# usb-led.net
KiCad netlist of a schematic drawn in EAGLE
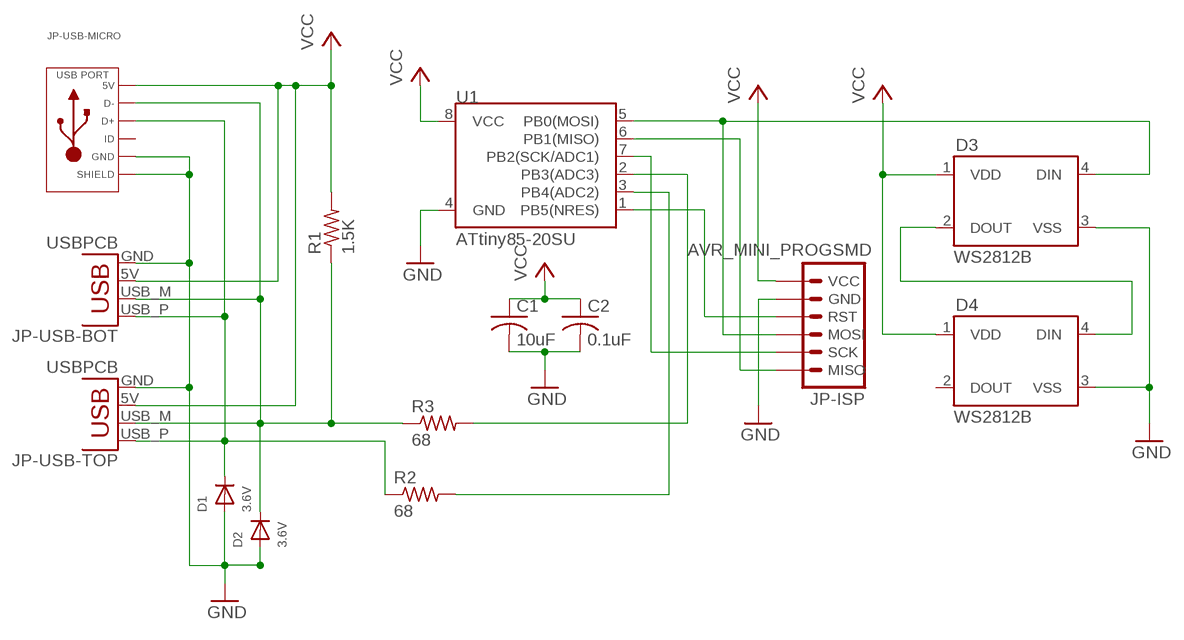
[diagram p0: schematic, sheet 1]

(export (version "E")
  (design (tool "Eeschema 10.0.6"))
  (components
    (comp (ref "C1")
      (value "10uF")
      (footprint "eagle-import:C0402")
      (libsource (lib "eagle-import") (part "C-USC0402"))
    )
    (comp (ref "C2")
      (value "0.1uF")
      (footprint "eagle-import:C0402")
      (libsource (lib "eagle-import") (part "C-USC0402"))
    )
    (comp (ref "D1")
      (value "3.6V")
      (footprint "eagle-import:SOD-523")
      (libsource (lib "eagle-import") (part "DIODESOD-523"))
    )
    (comp (ref "D2")
      (value "3.6V")
      (footprint "eagle-import:SOD-523")
      (libsource (lib "eagle-import") (part "DIODESOD-523"))
    )
    (comp (ref "D3")
      (value "WS2812B")
      (footprint "eagle-import:WS2812B")
      (libsource (lib "eagle-import") (part "WS2812B"))
    )
    (comp (ref "D4")
      (value "WS2812B")
      (footprint "eagle-import:WS2812B")
      (libsource (lib "eagle-import") (part "WS2812B"))
    )
    (comp (ref "JP-ISP")
      (value "AVR_MINI_PROGSMD")
      (footprint "eagle-import:AVR_MINI_PROG")
      (libsource (lib "eagle-import") (part "AVR_MINI_PROGSMD"))
    )
    (comp (ref "JP-USB-BOT")
      (value "USBPCB")
      (footprint "eagle-import:USB-A-PCB")
      (libsource (lib "eagle-import") (part "USBPCB"))
    )
    (comp (ref "JP-USB-MICRO")
      (value "USB_MICRO_RIGHT")
      (footprint "eagle-import:MICROUSB-RIGHT")
      (libsource (lib "eagle-import") (part "USB_MICRO_RIGHT"))
    )
    (comp (ref "JP-USB-TOP")
      (value "USBPCB")
      (footprint "eagle-import:USB-A-PCB")
      (libsource (lib "eagle-import") (part "USBPCB"))
    )
    (comp (ref "R1")
      (value "1.5K")
      (footprint "eagle-import:R0402")
      (libsource (lib "eagle-import") (part "R-US_R0402"))
    )
    (comp (ref "R2")
      (value "68")
      (footprint "eagle-import:R0402")
      (libsource (lib "eagle-import") (part "R-US_R0402"))
    )
    (comp (ref "R3")
      (value "68")
      (footprint "eagle-import:R0402")
      (libsource (lib "eagle-import") (part "R-US_R0402"))
    )
    (comp (ref "U1")
      (value "ATtiny85-20SU")
      (footprint "eagle-import:SO08-EIAJ")
      (libsource (lib "eagle-import") (part "ATTINY45TINY85-20-SMT"))
    )
  )
  (nets
    (net (code "1") (name "GND") (class "Default")
      (node (ref "C1") (pin "2") (pinfunction "2_2") (pintype "passive"))
      (node (ref "C2") (pin "2") (pinfunction "2_2") (pintype "passive"))
      (node (ref "D1") (pin "A") (pinfunction "A_A") (pintype "passive"))
      (node (ref "D2") (pin "A") (pinfunction "A_A") (pintype "passive"))
      (node (ref "D3") (pin "3") (pinfunction "VSS_3") (pintype "power_in"))
      (node (ref "D4") (pin "3") (pinfunction "VSS_3") (pintype "power_in"))
      (node (ref "JP-ISP") (pin "2") (pinfunction "GND_2") (pintype "passive"))
      (node (ref "JP-USB-BOT") (pin "GND") (pinfunction "GND_GND") (pintype "bidirectional"))
      (node (ref "JP-USB-MICRO") (pin "5") (pinfunction "GND_5") (pintype "power_in"))
      (node (ref "JP-USB-MICRO") (pin "S1") (pinfunction "SLD_S1") (pintype "power_in"))
      (node (ref "JP-USB-MICRO") (pin "S2") (pinfunction "SLD_S2") (pintype "power_in"))
      (node (ref "JP-USB-MICRO") (pin "S3") (pinfunction "SLD_S3") (pintype "power_in"))
      (node (ref "JP-USB-MICRO") (pin "S4") (pinfunction "SLD_S4") (pintype "power_in"))
      (node (ref "JP-USB-MICRO") (pin "S5") (pinfunction "SLD_S5") (pintype "power_in"))
      (node (ref "JP-USB-MICRO") (pin "S6") (pinfunction "SLD_S6") (pintype "power_in"))
      (node (ref "JP-USB-TOP") (pin "GND") (pinfunction "GND_GND") (pintype "bidirectional"))
      (node (ref "U1") (pin "4") (pinfunction "GND_4") (pintype "bidirectional"))
    )
    (net (code "2") (name "Net-(D1-C)") (class "Default")
      (node (ref "D1") (pin "K") (pinfunction "C_K") (pintype "passive"))
      (node (ref "JP-USB-BOT") (pin "USB_P") (pinfunction "D+_USB_P") (pintype "bidirectional"))
      (node (ref "JP-USB-MICRO") (pin "3") (pinfunction "D+_3") (pintype "bidirectional"))
      (node (ref "JP-USB-TOP") (pin "USB_P") (pinfunction "D+_USB_P") (pintype "bidirectional"))
      (node (ref "R2") (pin "1") (pinfunction "1_1") (pintype "passive"))
    )
    (net (code "3") (name "Net-(D2-C)") (class "Default")
      (node (ref "D2") (pin "K") (pinfunction "C_K") (pintype "passive"))
      (node (ref "JP-USB-BOT") (pin "USB_M") (pinfunction "D-_USB_M") (pintype "bidirectional"))
      (node (ref "JP-USB-MICRO") (pin "2") (pinfunction "D-_2") (pintype "bidirectional"))
      (node (ref "JP-USB-TOP") (pin "USB_M") (pinfunction "D-_USB_M") (pintype "bidirectional"))
      (node (ref "R1") (pin "1") (pinfunction "1_1") (pintype "passive"))
      (node (ref "R3") (pin "1") (pinfunction "1_1") (pintype "passive"))
    )
    (net (code "4") (name "Net-(D3-DIN)") (class "Default")
      (node (ref "D3") (pin "4") (pinfunction "DIN_4") (pintype "input"))
      (node (ref "JP-ISP") (pin "4") (pinfunction "MOSI_4") (pintype "passive"))
      (node (ref "U1") (pin "5") (pinfunction "PB0(MOSI)_5") (pintype "bidirectional"))
    )
    (net (code "5") (name "Net-(D3-DOUT)") (class "Default")
      (node (ref "D3") (pin "2") (pinfunction "DOUT_2") (pintype "output"))
      (node (ref "D4") (pin "4") (pinfunction "DIN_4") (pintype "input"))
    )
    (net (code "6") (name "Net-(JP-ISP-MISO)") (class "Default")
      (node (ref "JP-ISP") (pin "6") (pinfunction "MISO_6") (pintype "passive"))
      (node (ref "U1") (pin "6") (pinfunction "PB1(MISO)_6") (pintype "bidirectional"))
    )
    (net (code "7") (name "Net-(JP-ISP-RST)") (class "Default")
      (node (ref "JP-ISP") (pin "3") (pinfunction "RST_3") (pintype "passive"))
      (node (ref "U1") (pin "1") (pinfunction "PB5(NRES)_1") (pintype "bidirectional"))
    )
    (net (code "8") (name "Net-(JP-ISP-SCK)") (class "Default")
      (node (ref "JP-ISP") (pin "5") (pinfunction "SCK_5") (pintype "passive"))
      (node (ref "U1") (pin "7") (pinfunction "PB2(SCK/ADC1)_7") (pintype "bidirectional"))
    )
    (net (code "9") (name "Net-(U1-PB3(ADC3))") (class "Default")
      (node (ref "R3") (pin "2") (pinfunction "2_2") (pintype "passive"))
      (node (ref "U1") (pin "2") (pinfunction "PB3(ADC3)_2") (pintype "bidirectional"))
    )
    (net (code "10") (name "Net-(U1-PB4(ADC2))") (class "Default")
      (node (ref "R2") (pin "2") (pinfunction "2_2") (pintype "passive"))
      (node (ref "U1") (pin "3") (pinfunction "PB4(ADC2)_3") (pintype "bidirectional"))
    )
    (net (code "11") (name "VCC") (class "Default")
      (node (ref "C1") (pin "1") (pinfunction "1_1") (pintype "passive"))
      (node (ref "C2") (pin "1") (pinfunction "1_1") (pintype "passive"))
      (node (ref "D3") (pin "1") (pinfunction "VDD_1") (pintype "power_in"))
      (node (ref "D4") (pin "1") (pinfunction "VDD_1") (pintype "power_in"))
      (node (ref "JP-ISP") (pin "1") (pinfunction "VCC_1") (pintype "passive"))
      (node (ref "JP-USB-BOT") (pin "5V") (pinfunction "VBUS_5V") (pintype "bidirectional"))
      (node (ref "JP-USB-MICRO") (pin "1") (pinfunction "5V_1") (pintype "power_in"))
      (node (ref "JP-USB-TOP") (pin "5V") (pinfunction "VBUS_5V") (pintype "bidirectional"))
      (node (ref "R1") (pin "2") (pinfunction "2_2") (pintype "passive"))
      (node (ref "U1") (pin "8") (pinfunction "VCC_8") (pintype "bidirectional"))
    )
    (net (code "12") (name "unconnected-(D4-DOUT-Pad2)") (class "Default")
      (node (ref "D4") (pin "2") (pinfunction "DOUT_2") (pintype "output"))
    )
    (net (code "13") (name "unconnected-(JP-USB-MICRO-ID-Pad4)") (class "Default")
      (node (ref "JP-USB-MICRO") (pin "4") (pinfunction "ID_4") (pintype "bidirectional"))
    )
  )
)
